# controller_rev4_2.net
KiCad netlist of a schematic drawn in EAGLE
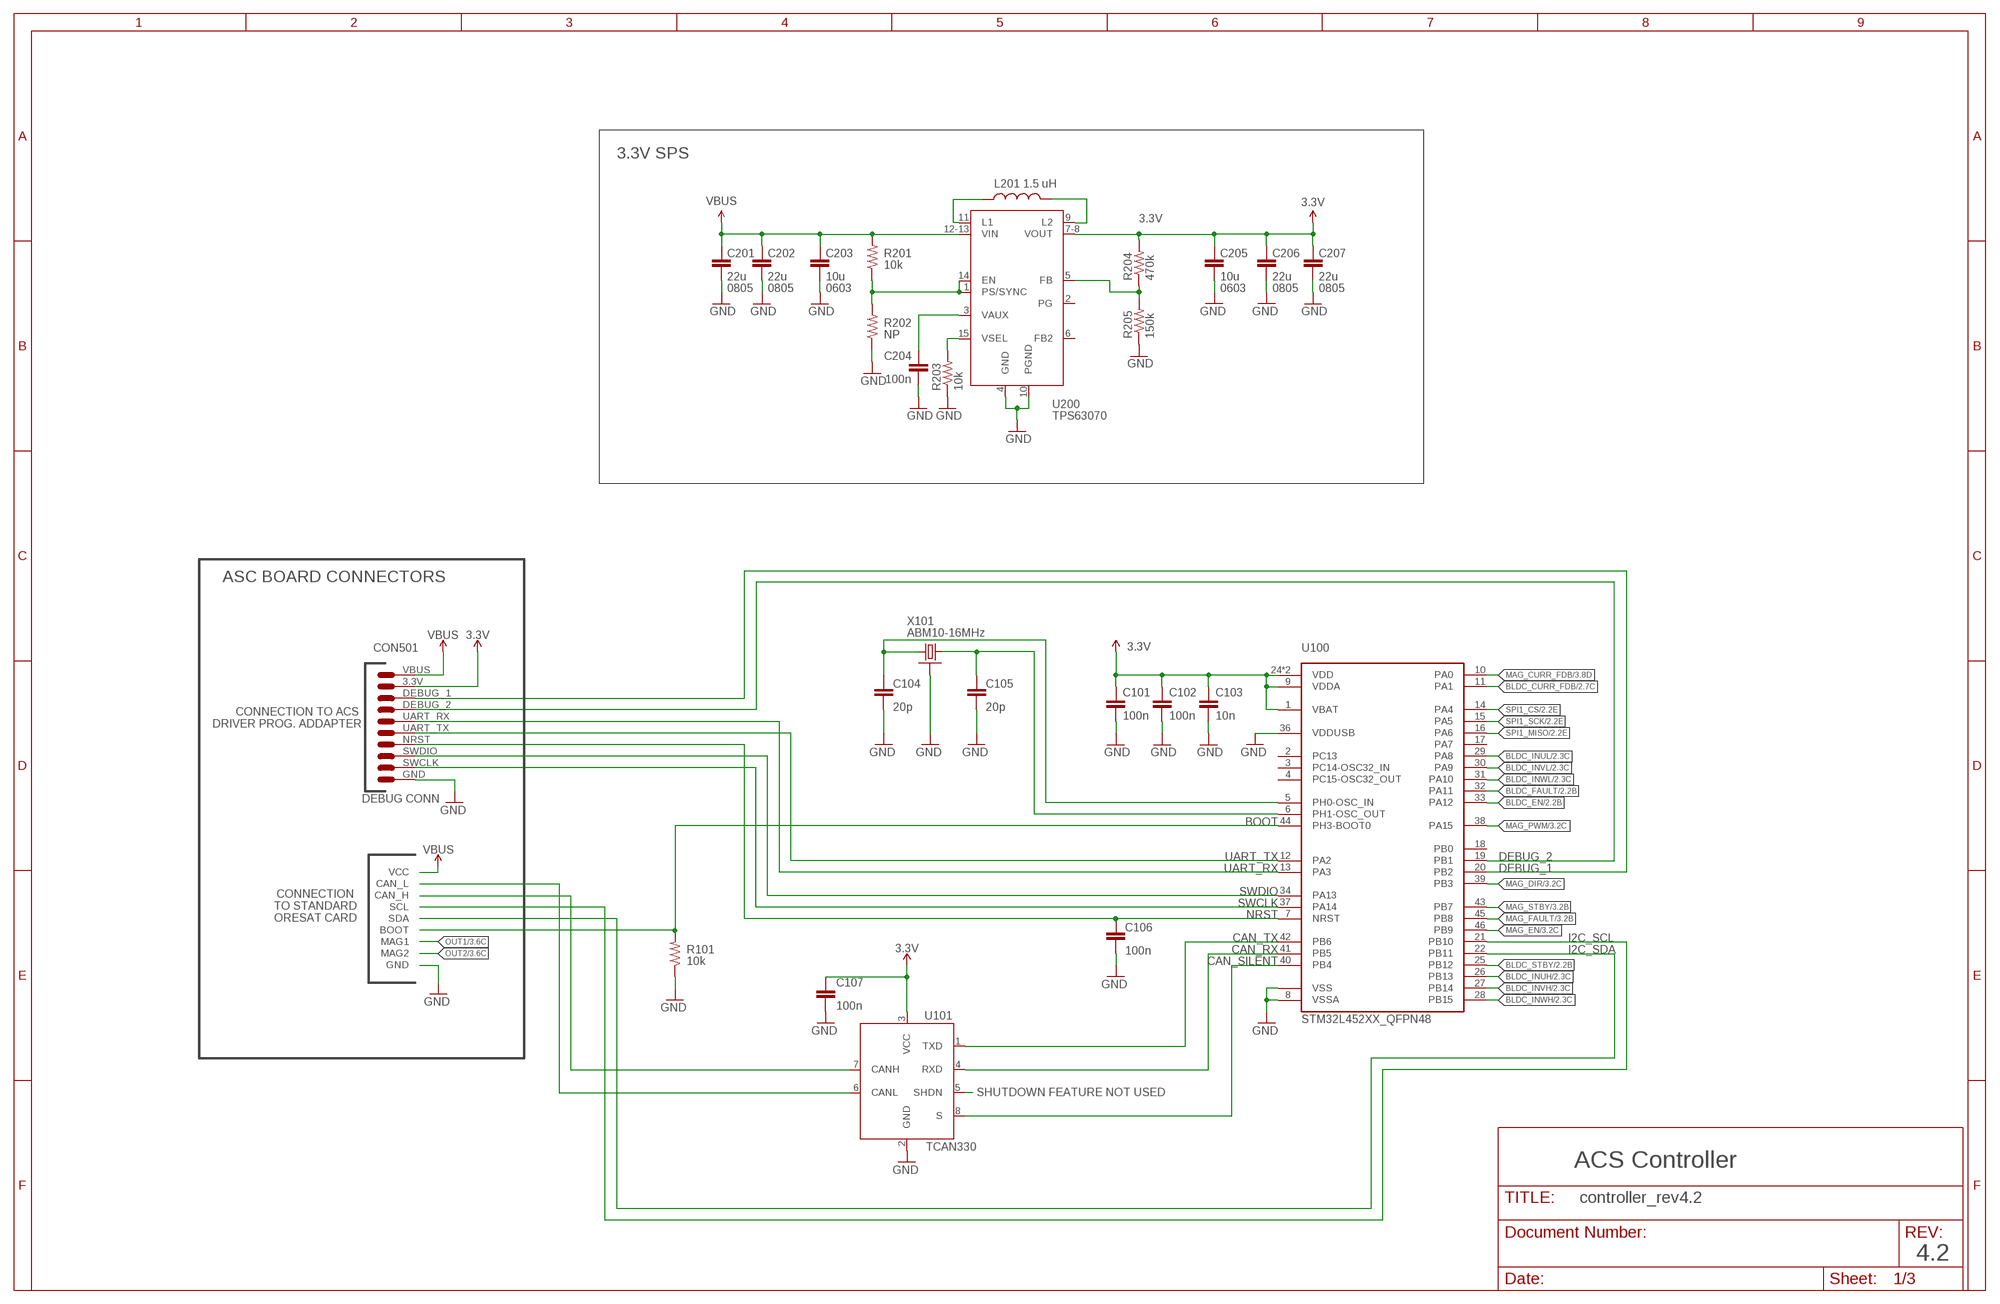
[diagram p0: schematic, sheet 1]
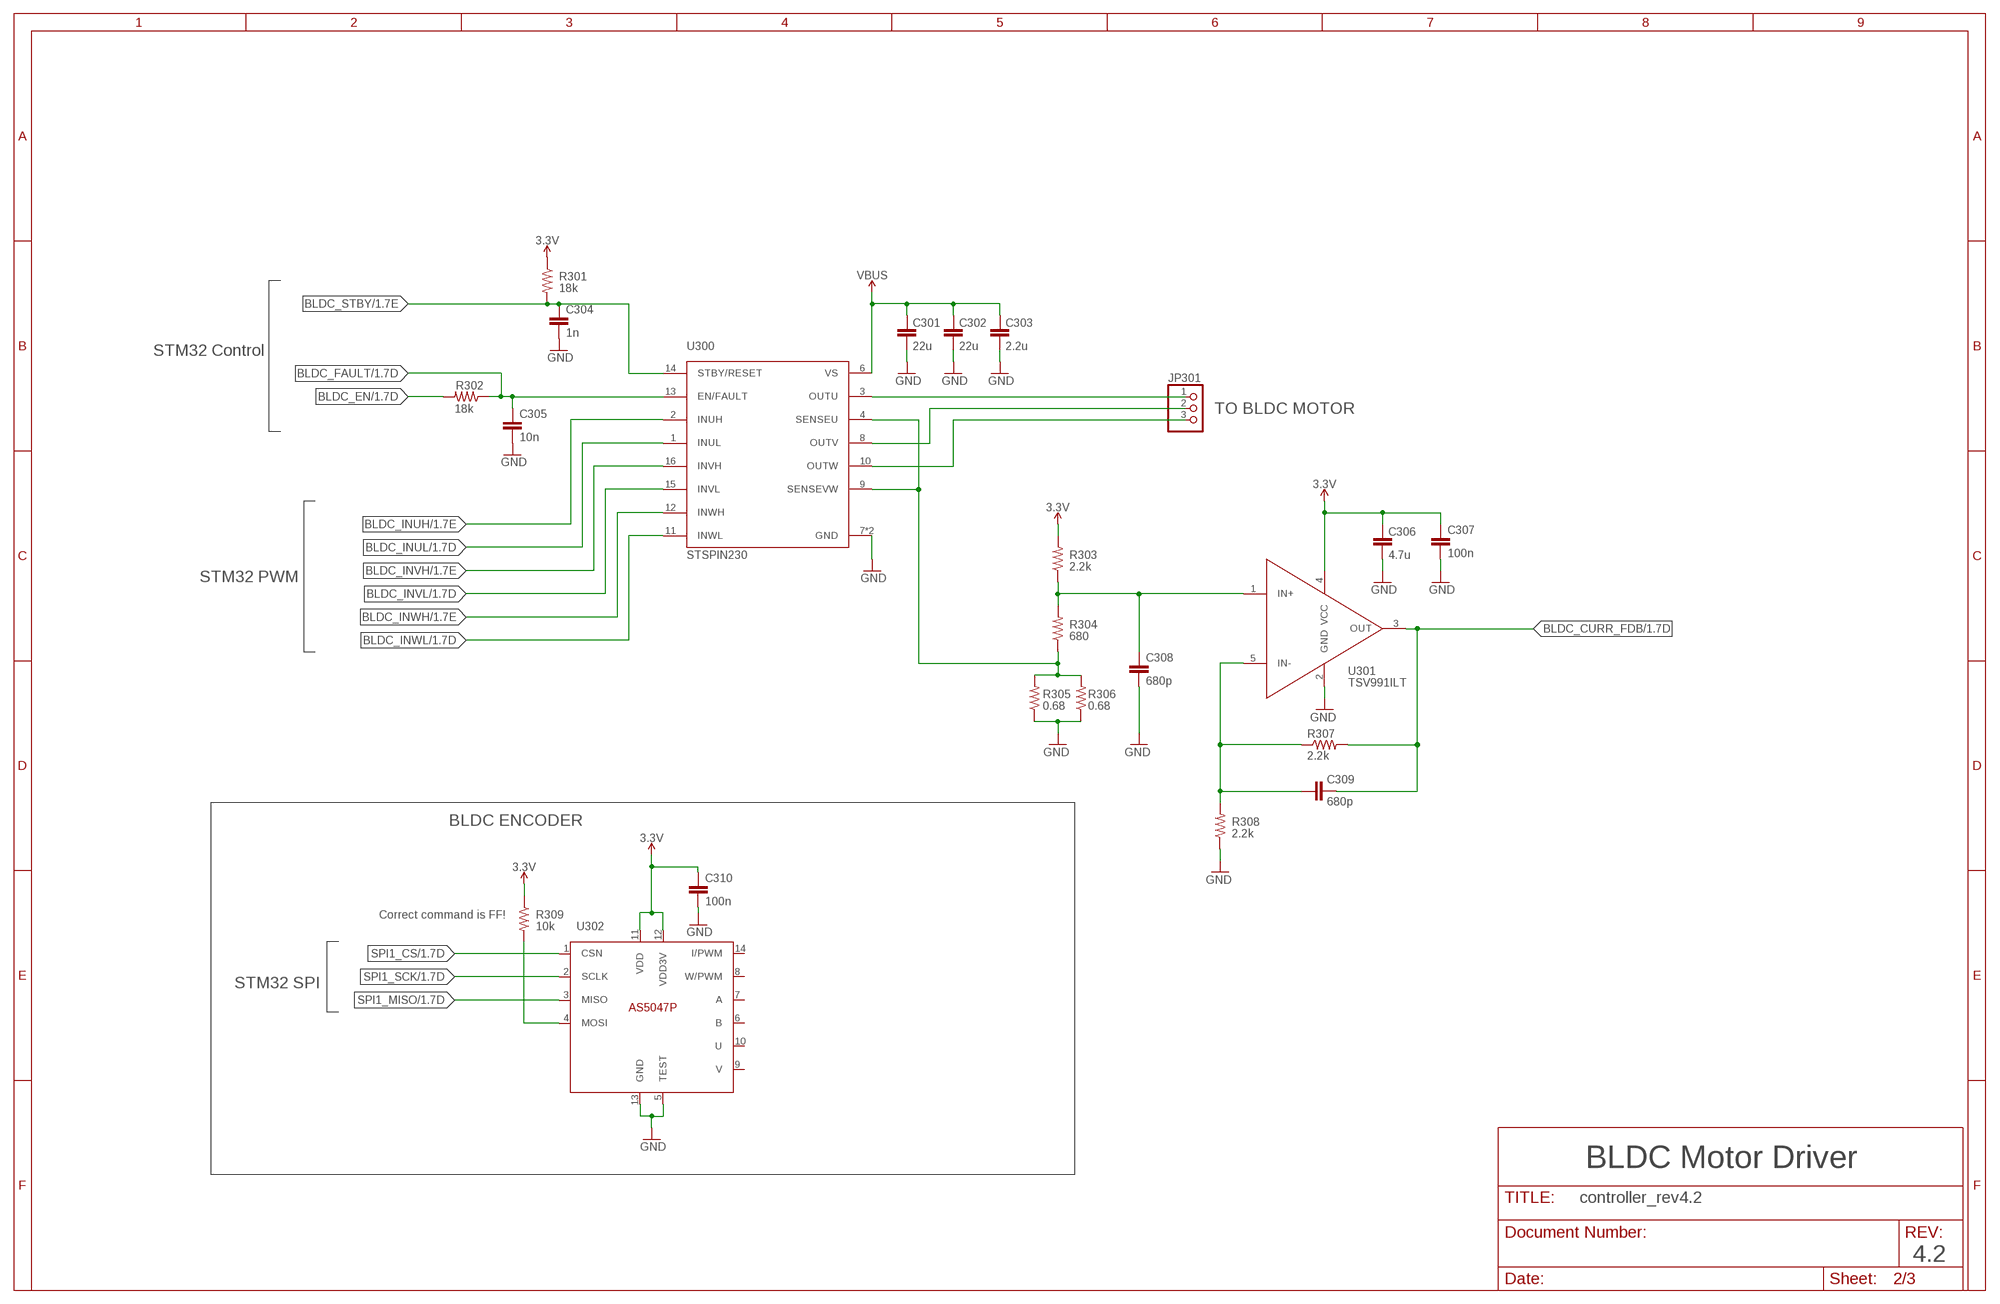
[diagram p1: schematic, sheet 2]
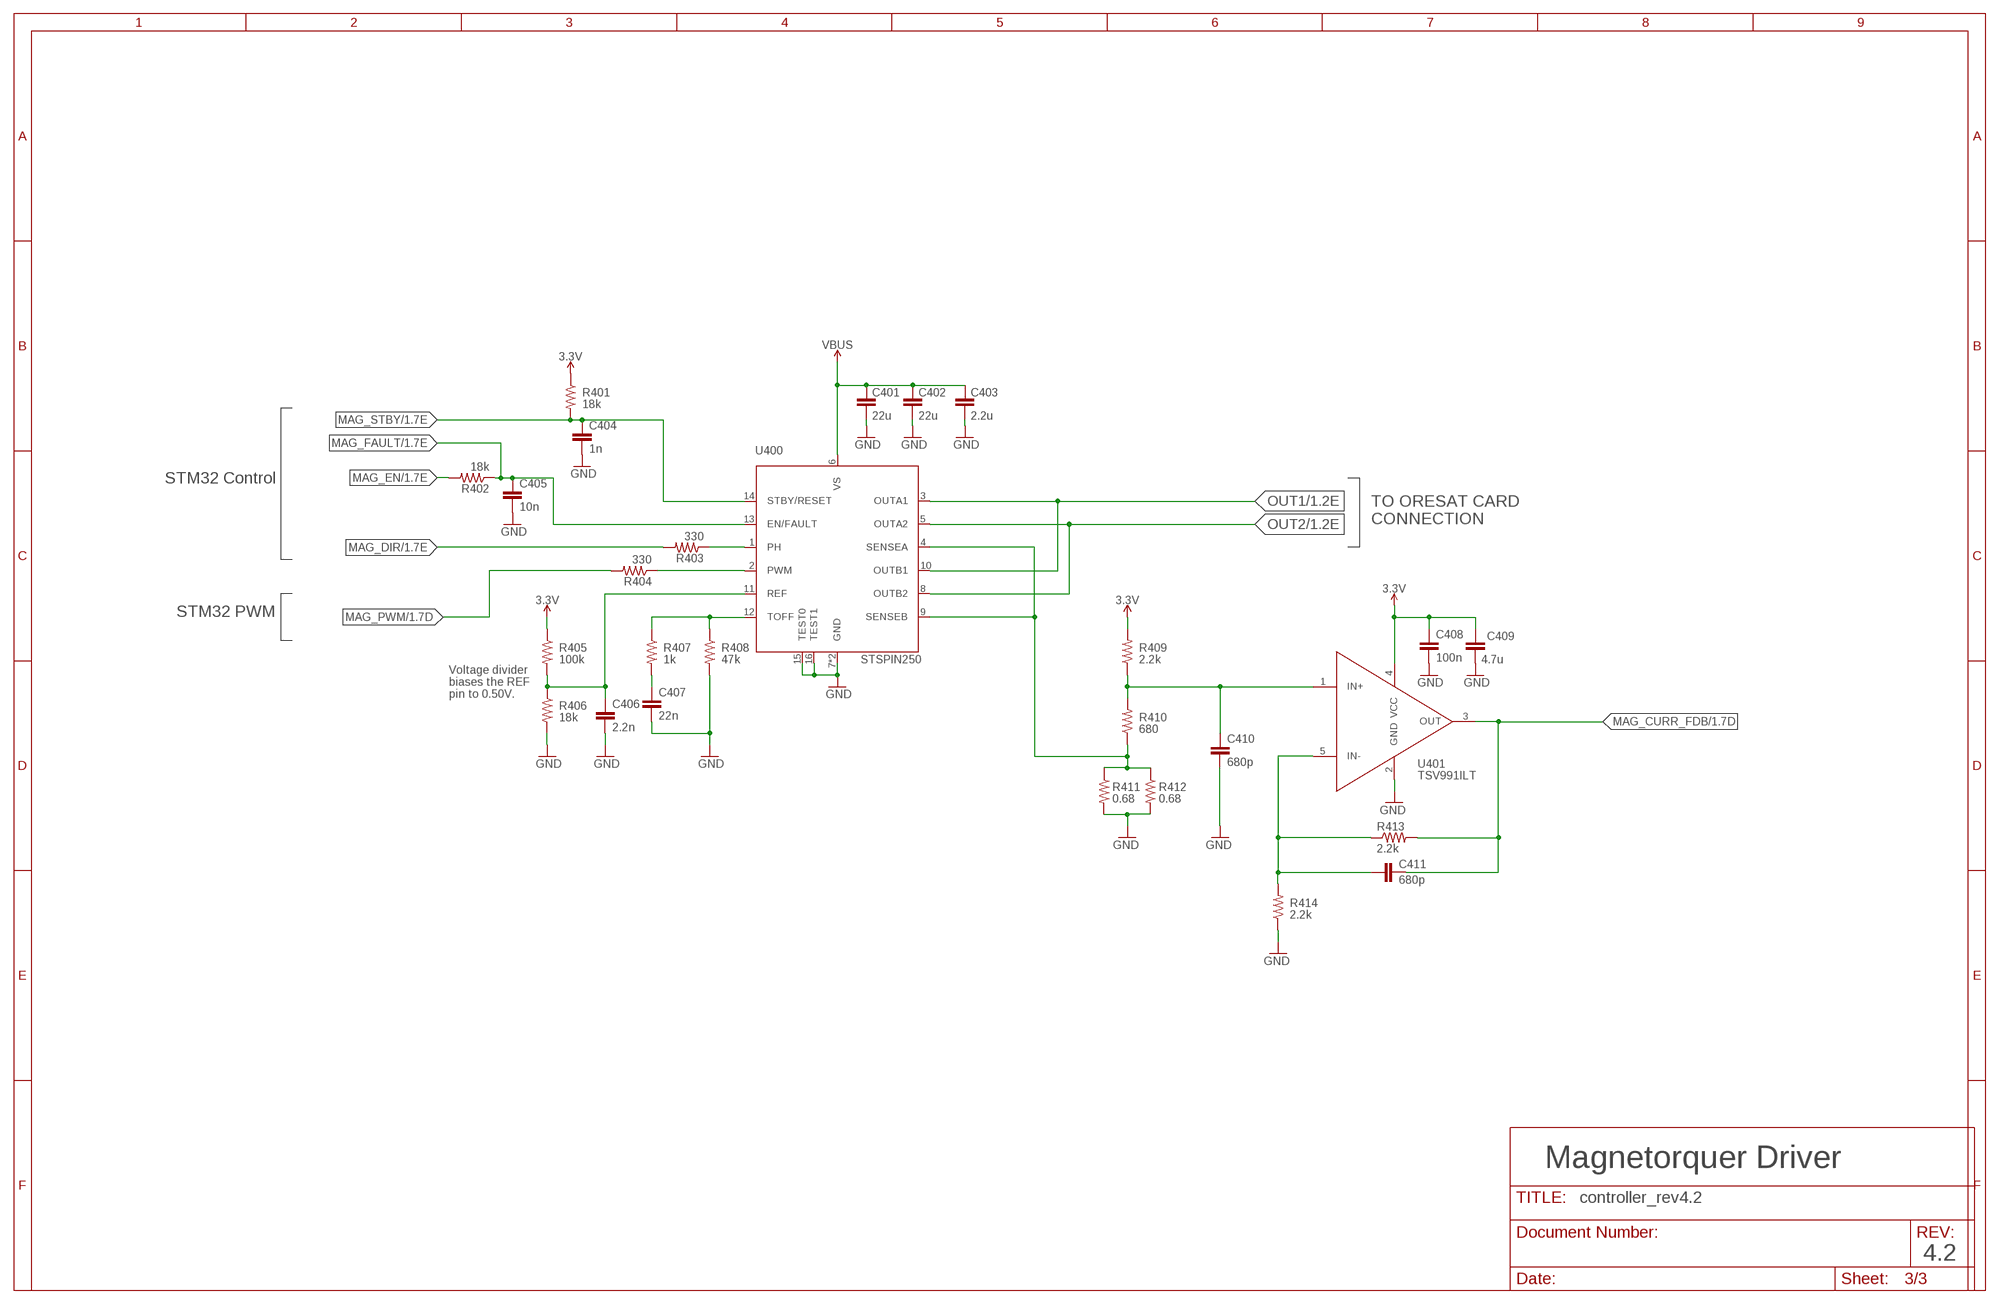
[diagram p2: schematic, sheet 3]

(export (version "E")
  (design (tool "Eeschema 10.0.6"))
  (components
    (comp (ref "C301")
      (value "22u")
      (footprint "eagle-import:.0603-B-NOSILK")
      (fields (field (name "MFR") "Samsung") (field (name "MPN") "CL05B104KO5NNNC"))
      (libsource (lib "eagle-import") (part "C-EU0603-B-NOSILK"))
    )
    (comp (ref "C302")
      (value "22u")
      (footprint "eagle-import:.0603-B-NOSILK")
      (fields (field (name "MFR") "Samsung") (field (name "MPN") "CL05B104KO5NNNC"))
      (libsource (lib "eagle-import") (part "C-EU0603-B-NOSILK"))
    )
    (comp (ref "C303")
      (value "2.2u")
      (footprint "eagle-import:.0603-B-NOSILK")
      (fields (field (name "MFR") "Samsung") (field (name "MPN") "CL05B104KO5NNNC"))
      (libsource (lib "eagle-import") (part "C-EU0603-B-NOSILK"))
    )
    (comp (ref "C304")
      (value "1n")
      (footprint "eagle-import:.0402-B-NOSILK")
      (fields (field (name "MFR") "Samsung") (field (name "MPN") "CL05B104KO5NNNC"))
      (libsource (lib "eagle-import") (part "rcl_custom_C-EU0402-B-NOSILK"))
    )
    (comp (ref "C305")
      (value "10n")
      (footprint "eagle-import:.0402-B-NOSILK")
      (fields (field (name "MFR") "Samsung") (field (name "MPN") "CL05B104KO5NNNC"))
      (libsource (lib "eagle-import") (part "rcl_custom_C-EU0402-B-NOSILK"))
    )
    (comp (ref "C306")
      (value "4.7u")
      (footprint "eagle-import:.0603-B-NOSILK")
      (fields (field (name "MFR") "Samsung") (field (name "MPN") "CL05B104KO5NNNC"))
      (libsource (lib "eagle-import") (part "C-EU0603-B-NOSILK"))
    )
    (comp (ref "C307")
      (value "100n")
      (footprint "eagle-import:.0402-B-NOSILK")
      (fields (field (name "MFR") "Samsung") (field (name "MPN") "CL05B104KO5NNNC"))
      (libsource (lib "eagle-import") (part "rcl_custom_C-EU0402-B-NOSILK"))
    )
    (comp (ref "C308")
      (value "680p")
      (footprint "eagle-import:.0402-B-NOSILK")
      (fields (field (name "MFR") "Samsung") (field (name "MPN") "CL05B104KO5NNNC"))
      (libsource (lib "eagle-import") (part "rcl_custom_C-EU0402-B-NOSILK"))
    )
    (comp (ref "C309")
      (value "680p")
      (footprint "eagle-import:.0402-B-NOSILK")
      (fields (field (name "MFR") "Samsung") (field (name "MPN") "CL05B104KO5NNNC"))
      (libsource (lib "eagle-import") (part "rcl_custom_C-EU0402-B-NOSILK"))
    )
    (comp (ref "C310")
      (value "100n")
      (footprint "eagle-import:.0402-B-NOSILK")
      (fields (field (name "MFR") "Samsung") (field (name "MPN") "CL05B104KO5NNNC"))
      (libsource (lib "eagle-import") (part "rcl_custom_C-EU0402-B-NOSILK"))
    )
    (comp (ref "JP301")
      (value "PINHD-1X03_2.00")
      (footprint "eagle-import:1X03M")
      (libsource (lib "eagle-import") (part "PINHD-1X03_2.00"))
    )
    (comp (ref "R301")
      (value "18k")
      (footprint "eagle-import:.0402-B-NOSILK")
      (fields (field (name "MFR") "Samsung") (field (name "MPN") "RC1005F6653CS"))
      (libsource (lib "eagle-import") (part "rcl_custom_R-US_0402-B-NOSILK"))
    )
    (comp (ref "R302")
      (value "18k")
      (footprint "eagle-import:.0402-B-NOSILK")
      (fields (field (name "MFR") "Samsung") (field (name "MPN") "RC1005F6653CS"))
      (libsource (lib "eagle-import") (part "rcl_custom_R-US_0402-B-NOSILK"))
    )
    (comp (ref "R303")
      (value "2.2k")
      (footprint "eagle-import:.0402-B-NOSILK")
      (fields (field (name "MFR") "Samsung") (field (name "MPN") "RC1005F6653CS"))
      (libsource (lib "eagle-import") (part "rcl_custom_R-US_0402-B-NOSILK"))
    )
    (comp (ref "R304")
      (value "680")
      (footprint "eagle-import:.0402-B-NOSILK")
      (fields (field (name "MFR") "Samsung") (field (name "MPN") "RC1005F6653CS"))
      (libsource (lib "eagle-import") (part "rcl_custom_R-US_0402-B-NOSILK"))
    )
    (comp (ref "R305")
      (value "0.68")
      (footprint "eagle-import:.0805-B-NOSILK")
      (libsource (lib "eagle-import") (part "R-US_0805-B-NOSILK"))
    )
    (comp (ref "R306")
      (value "0.68")
      (footprint "eagle-import:.0805-B-NOSILK")
      (libsource (lib "eagle-import") (part "R-US_0805-B-NOSILK"))
    )
    (comp (ref "R307")
      (value "2.2k")
      (footprint "eagle-import:.0402-B-NOSILK")
      (fields (field (name "MFR") "Samsung") (field (name "MPN") "RC1005F6653CS"))
      (libsource (lib "eagle-import") (part "rcl_custom_R-US_0402-B-NOSILK"))
    )
    (comp (ref "R308")
      (value "2.2k")
      (footprint "eagle-import:.0402-B-NOSILK")
      (fields (field (name "MFR") "Samsung") (field (name "MPN") "RC1005F6653CS"))
      (libsource (lib "eagle-import") (part "rcl_custom_R-US_0402-B-NOSILK"))
    )
    (comp (ref "R309")
      (value "10k")
      (footprint "eagle-import:.0402-B-NOSILK")
      (fields (field (name "MFR") "Samsung") (field (name "MPN") "RC1005F6653CS"))
      (libsource (lib "eagle-import") (part "rcl_custom_R-US_0402-B-NOSILK"))
    )
    (comp (ref "U300")
      (value "STSPIN230")
      (footprint "eagle-import:VFQPN")
      (libsource (lib "eagle-import") (part "STSPIN230"))
    )
    (comp (ref "U301")
      (value "TSV991ILT")
      (footprint "eagle-import:SOT23-5")
      (libsource (lib "eagle-import") (part "TSV991ILT"))
    )
    (comp (ref "U302")
      (value "AS5047P")
      (footprint "eagle-import:TSSOP14")
      (libsource (lib "eagle-import") (part "AS5047P"))
    )
    (comp (ref "C401")
      (value "22u")
      (footprint "eagle-import:.0603-B-NOSILK")
      (fields (field (name "MFR") "Samsung") (field (name "MPN") "CL05B104KO5NNNC"))
      (libsource (lib "eagle-import") (part "C-EU0603-B-NOSILK"))
    )
    (comp (ref "C402")
      (value "22u")
      (footprint "eagle-import:.0603-B-NOSILK")
      (fields (field (name "MFR") "Samsung") (field (name "MPN") "CL05B104KO5NNNC"))
      (libsource (lib "eagle-import") (part "C-EU0603-B-NOSILK"))
    )
    (comp (ref "C403")
      (value "2.2u")
      (footprint "eagle-import:.0603-B-NOSILK")
      (fields (field (name "MFR") "Samsung") (field (name "MPN") "CL05B104KO5NNNC"))
      (libsource (lib "eagle-import") (part "C-EU0603-B-NOSILK"))
    )
    (comp (ref "C404")
      (value "1n")
      (footprint "eagle-import:.0402-B-NOSILK")
      (fields (field (name "MFR") "Samsung") (field (name "MPN") "CL05B104KO5NNNC"))
      (libsource (lib "eagle-import") (part "rcl_custom_C-EU0402-B-NOSILK"))
    )
    (comp (ref "C405")
      (value "10n")
      (footprint "eagle-import:.0402-B-NOSILK")
      (fields (field (name "MFR") "Samsung") (field (name "MPN") "CL05B104KO5NNNC"))
      (libsource (lib "eagle-import") (part "rcl_custom_C-EU0402-B-NOSILK"))
    )
    (comp (ref "C406")
      (value "2.2n")
      (footprint "eagle-import:.0402-B-NOSILK")
      (fields (field (name "MFR") "Samsung") (field (name "MPN") "CL05B104KO5NNNC"))
      (libsource (lib "eagle-import") (part "rcl_custom_C-EU0402-B-NOSILK"))
    )
    (comp (ref "C407")
      (value "22n")
      (footprint "eagle-import:.0402-B-NOSILK")
      (fields (field (name "MFR") "Samsung") (field (name "MPN") "CL05B104KO5NNNC"))
      (libsource (lib "eagle-import") (part "rcl_custom_C-EU0402-B-NOSILK"))
    )
    (comp (ref "C408")
      (value "100n")
      (footprint "eagle-import:.0402-B-NOSILK")
      (fields (field (name "MFR") "Samsung") (field (name "MPN") "CL05B104KO5NNNC"))
      (libsource (lib "eagle-import") (part "rcl_custom_C-EU0402-B-NOSILK"))
    )
    (comp (ref "C409")
      (value "4.7u")
      (footprint "eagle-import:.0603-B-NOSILK")
      (fields (field (name "MFR") "Samsung") (field (name "MPN") "CL05B104KO5NNNC"))
      (libsource (lib "eagle-import") (part "C-EU0603-B-NOSILK"))
    )
    (comp (ref "C410")
      (value "680p")
      (footprint "eagle-import:.0402-B-NOSILK")
      (fields (field (name "MFR") "Samsung") (field (name "MPN") "CL05B104KO5NNNC"))
      (libsource (lib "eagle-import") (part "rcl_custom_C-EU0402-B-NOSILK"))
    )
    (comp (ref "C411")
      (value "680p")
      (footprint "eagle-import:.0402-B-NOSILK")
      (fields (field (name "MFR") "Samsung") (field (name "MPN") "CL05B104KO5NNNC"))
      (libsource (lib "eagle-import") (part "rcl_custom_C-EU0402-B-NOSILK"))
    )
    (comp (ref "R401")
      (value "18k")
      (footprint "eagle-import:.0402-B-NOSILK")
      (fields (field (name "MFR") "Samsung") (field (name "MPN") "RC1005F6653CS"))
      (libsource (lib "eagle-import") (part "rcl_custom_R-US_0402-B-NOSILK"))
    )
    (comp (ref "R402")
      (value "18k")
      (footprint "eagle-import:.0402-B-NOSILK")
      (fields (field (name "MFR") "Samsung") (field (name "MPN") "RC1005F6653CS"))
      (libsource (lib "eagle-import") (part "rcl_custom_R-US_0402-B-NOSILK"))
    )
    (comp (ref "R403")
      (value "330")
      (footprint "eagle-import:.0402-B-NOSILK")
      (fields (field (name "MFR") "Samsung") (field (name "MPN") "RC1005F6653CS"))
      (libsource (lib "eagle-import") (part "rcl_custom_R-US_0402-B-NOSILK"))
    )
    (comp (ref "R404")
      (value "330")
      (footprint "eagle-import:.0402-B-NOSILK")
      (fields (field (name "MFR") "Samsung") (field (name "MPN") "RC1005F6653CS"))
      (libsource (lib "eagle-import") (part "rcl_custom_R-US_0402-B-NOSILK"))
    )
    (comp (ref "R405")
      (value "100k")
      (footprint "eagle-import:.0402-B-NOSILK")
      (fields (field (name "MFR") "Samsung") (field (name "MPN") "RC1005F6653CS"))
      (libsource (lib "eagle-import") (part "rcl_custom_R-US_0402-B-NOSILK"))
    )
    (comp (ref "R406")
      (value "18k")
      (footprint "eagle-import:.0402-B-NOSILK")
      (fields (field (name "MFR") "Samsung") (field (name "MPN") "RC1005F6653CS"))
      (libsource (lib "eagle-import") (part "rcl_custom_R-US_0402-B-NOSILK"))
    )
    (comp (ref "R407")
      (value "1k")
      (footprint "eagle-import:.0402-B-NOSILK")
      (fields (field (name "MFR") "Samsung") (field (name "MPN") "RC1005F6653CS"))
      (libsource (lib "eagle-import") (part "rcl_custom_R-US_0402-B-NOSILK"))
    )
    (comp (ref "R408")
      (value "47k")
      (footprint "eagle-import:.0402-B-NOSILK")
      (fields (field (name "MFR") "Samsung") (field (name "MPN") "RC1005F6653CS"))
      (libsource (lib "eagle-import") (part "rcl_custom_R-US_0402-B-NOSILK"))
    )
    (comp (ref "R409")
      (value "2.2k")
      (footprint "eagle-import:.0402-B-NOSILK")
      (fields (field (name "MFR") "Samsung") (field (name "MPN") "RC1005F6653CS"))
      (libsource (lib "eagle-import") (part "rcl_custom_R-US_0402-B-NOSILK"))
    )
    (comp (ref "R410")
      (value "680")
      (footprint "eagle-import:.0402-B-NOSILK")
      (fields (field (name "MFR") "Samsung") (field (name "MPN") "RC1005F6653CS"))
      (libsource (lib "eagle-import") (part "rcl_custom_R-US_0402-B-NOSILK"))
    )
    (comp (ref "R411")
      (value "0.68")
      (footprint "eagle-import:.0805-B-NOSILK")
      (libsource (lib "eagle-import") (part "R-US_0805-B-NOSILK"))
    )
    (comp (ref "R412")
      (value "0.68")
      (footprint "eagle-import:.0805-B-NOSILK")
      (libsource (lib "eagle-import") (part "R-US_0805-B-NOSILK"))
    )
    (comp (ref "R413")
      (value "2.2k")
      (footprint "eagle-import:.0402-B-NOSILK")
      (fields (field (name "MFR") "Samsung") (field (name "MPN") "RC1005F6653CS"))
      (libsource (lib "eagle-import") (part "rcl_custom_R-US_0402-B-NOSILK"))
    )
    (comp (ref "R414")
      (value "2.2k")
      (footprint "eagle-import:.0402-B-NOSILK")
      (fields (field (name "MFR") "Samsung") (field (name "MPN") "RC1005F6653CS"))
      (libsource (lib "eagle-import") (part "rcl_custom_R-US_0402-B-NOSILK"))
    )
    (comp (ref "U400")
      (value "STSPIN250")
      (footprint "eagle-import:VFQPN")
      (libsource (lib "eagle-import") (part "STSPIN250"))
    )
    (comp (ref "U401")
      (value "TSV991ILT")
      (footprint "eagle-import:SOT23-5")
      (libsource (lib "eagle-import") (part "TSV991ILT"))
    )
    (comp (ref "C101")
      (value "100n")
      (footprint "eagle-import:.0402-B-NOSILK")
      (fields (field (name "MFR") "Samsung") (field (name "MPN") "CL05B104KO5NNNC"))
      (libsource (lib "eagle-import") (part "rcl_custom_C-EU0402-B-NOSILK"))
    )
    (comp (ref "C102")
      (value "100n")
      (footprint "eagle-import:.0402-B-NOSILK")
      (fields (field (name "MFR") "Samsung") (field (name "MPN") "CL05B104KO5NNNC"))
      (libsource (lib "eagle-import") (part "rcl_custom_C-EU0402-B-NOSILK"))
    )
    (comp (ref "C103")
      (value "10n")
      (footprint "eagle-import:.0402-B-NOSILK")
      (fields (field (name "MFR") "Samsung") (field (name "MPN") "CL05B104KO5NNNC"))
      (libsource (lib "eagle-import") (part "rcl_custom_C-EU0402-B-NOSILK"))
    )
    (comp (ref "C104")
      (value "20p")
      (footprint "eagle-import:.0402-B-NOSILK")
      (fields (field (name "MFR") "Samsung") (field (name "MPN") "CL05C200JB51PNC"))
      (libsource (lib "eagle-import") (part "rcl_custom_C-EU0402-B-NOSILK"))
    )
    (comp (ref "C105")
      (value "20p")
      (footprint "eagle-import:.0402-B-NOSILK")
      (fields (field (name "MFR") "Samsung") (field (name "MPN") "CL05C200JB51PNC"))
      (libsource (lib "eagle-import") (part "rcl_custom_C-EU0402-B-NOSILK"))
    )
    (comp (ref "C106")
      (value "100n")
      (footprint "eagle-import:.0402-B-NOSILK")
      (fields (field (name "MFR") "Samsung") (field (name "MPN") "CL05C200JB51PNC"))
      (libsource (lib "eagle-import") (part "rcl_custom_C-EU0402-B-NOSILK"))
    )
    (comp (ref "C107")
      (value "100n")
      (footprint "eagle-import:.0402-B-NOSILK")
      (fields (field (name "MFR") "Samsung") (field (name "MPN") "CL05B104KO5NNNC"))
      (libsource (lib "eagle-import") (part "rcl_custom_C-EU0402-B-NOSILK"))
    )
    (comp (ref "C201")
      (value "22u")
      (footprint "eagle-import:.0805-B-NOSILK")
      (libsource (lib "eagle-import") (part "C-EU0805-B-NOSILK"))
    )
    (comp (ref "C202")
      (value "22u")
      (footprint "eagle-import:.0805-B-NOSILK")
      (libsource (lib "eagle-import") (part "C-EU0805-B-NOSILK"))
    )
    (comp (ref "C203")
      (value "10u")
      (footprint "eagle-import:.0603-B-NOSILK")
      (fields (field (name "MFR") "Samsung") (field (name "MPN") "CL05B104KO5NNNC"))
      (libsource (lib "eagle-import") (part "C-EU0603-B-NOSILK"))
    )
    (comp (ref "C204")
      (value "100n")
      (footprint "eagle-import:.0402-B-NOSILK")
      (fields (field (name "MFR") "Samsung") (field (name "MPN") "CL05B104KO5NNNC"))
      (libsource (lib "eagle-import") (part "rcl_custom_C-EU0402-B-NOSILK"))
    )
    (comp (ref "C205")
      (value "10u")
      (footprint "eagle-import:.0603-B-NOSILK")
      (fields (field (name "MFR") "Samsung") (field (name "MPN") "CL05B104KO5NNNC"))
      (libsource (lib "eagle-import") (part "C-EU0603-B-NOSILK"))
    )
    (comp (ref "C206")
      (value "22u")
      (footprint "eagle-import:.0805-B-NOSILK")
      (libsource (lib "eagle-import") (part "C-EU0805-B-NOSILK"))
    )
    (comp (ref "C207")
      (value "22u")
      (footprint "eagle-import:.0805-B-NOSILK")
      (libsource (lib "eagle-import") (part "C-EU0805-B-NOSILK"))
    )
    (comp (ref "C501")
      (value "DEBUG_CON")
      (footprint "eagle-import:DEBUG_CON")
      (libsource (lib "eagle-import") (part "DEBUG_CON"))
    )
    (comp (ref "L201")
      (value "1.5 uH")
      (footprint "eagle-import:L-COILCRAFT-XFL4020")
      (fields (field (name "MFR") "Coilcraft") (field (name "MPN") "XFL4020-152ME"))
      (libsource (lib "eagle-import") (part "L-COILCRAFT-XFL4020"))
    )
    (comp (ref "R101")
      (value "10k")
      (footprint "eagle-import:.0402-B-NOSILK")
      (fields (field (name "MFR") "Samsung") (field (name "MPN") "RC1005F6653CS"))
      (libsource (lib "eagle-import") (part "rcl_custom_R-US_0402-B-NOSILK"))
    )
    (comp (ref "R201")
      (value "10k")
      (footprint "eagle-import:.0402-B-NOSILK")
      (fields (field (name "MFR") "Samsung") (field (name "MPN") "RC1005F6653CS"))
      (libsource (lib "eagle-import") (part "rcl_custom_R-US_0402-B-NOSILK"))
    )
    (comp (ref "R202")
      (value "NP")
      (footprint "eagle-import:.0402-B-NOSILK")
      (fields (field (name "MFR") "Samsung") (field (name "MPN") "RC1005F6653CS"))
      (libsource (lib "eagle-import") (part "rcl_custom_R-US_0402-B-NOSILK"))
    )
    (comp (ref "R203")
      (value "10k")
      (footprint "eagle-import:.0402-B-NOSILK")
      (fields (field (name "MFR") "Samsung") (field (name "MPN") "RC1005F6653CS"))
      (libsource (lib "eagle-import") (part "rcl_custom_R-US_0402-B-NOSILK"))
    )
    (comp (ref "R204")
      (value "470k")
      (footprint "eagle-import:.0402-B-NOSILK")
      (fields (field (name "MFR") "Samsung") (field (name "MPN") "RC1005F6653CS"))
      (libsource (lib "eagle-import") (part "rcl_custom_R-US_0402-B-NOSILK"))
    )
    (comp (ref "R205")
      (value "150k")
      (footprint "eagle-import:.0402-B-NOSILK")
      (fields (field (name "MFR") "Samsung") (field (name "MPN") "RC1005F6653CS"))
      (libsource (lib "eagle-import") (part "rcl_custom_R-US_0402-B-NOSILK"))
    )
    (comp (ref "U$1")
      (value "DRIVER-FLEX_CONN")
      (footprint "eagle-import:20-PAD_DRIVER-CONN")
      (libsource (lib "eagle-import") (part "DRIVER-FLEX_CONN"))
    )
    (comp (ref "U100")
      (value "STM32L452XX_QFPN48")
      (footprint "eagle-import:QFPN-48")
      (libsource (lib "eagle-import") (part "STM32L452XX_QFPN48"))
    )
    (comp (ref "U101")
      (value "TCAN330")
      (footprint "eagle-import:SOT23-8_TI-DCN")
      (fields (field (name "MFR") "Texas Instruments") (field (name "MPN") "TCAN330GDCNT"))
      (libsource (lib "eagle-import") (part "TCAN330"))
    )
    (comp (ref "U200")
      (value "TPS63070")
      (footprint "eagle-import:TPS63070X")
      (fields (field (name "MFR") "TI"))
      (libsource (lib "eagle-import") (part "TPS63070X"))
    )
    (comp (ref "X101")
      (value "ABM10-16MHz")
      (footprint "eagle-import:CRYSTAL_2.5X2")
      (fields (field (name "MFR") "ECS Inc.") (field (name "MPN") "ECS-160-10-36Q-ES-TR"))
      (libsource (lib "eagle-import") (part "CRYSTAL-WITH-GND"))
    )
  )
  (nets
    (net (code "1") (name "3.3V") (class "Default")
      (node (ref "C101") (pin "1") (pinfunction "1_1") (pintype "passive"))
      (node (ref "C102") (pin "1") (pinfunction "1_1") (pintype "passive"))
      (node (ref "C103") (pin "1") (pinfunction "1_1") (pintype "passive"))
      (node (ref "C107") (pin "1") (pinfunction "1_1") (pintype "passive"))
      (node (ref "C205") (pin "1") (pinfunction "1_1") (pintype "passive"))
      (node (ref "C206") (pin "1") (pinfunction "1_1") (pintype "passive"))
      (node (ref "C207") (pin "1") (pinfunction "1_1") (pintype "passive"))
      (node (ref "C306") (pin "1") (pinfunction "1_1") (pintype "passive"))
      (node (ref "C307") (pin "1") (pinfunction "1_1") (pintype "passive"))
      (node (ref "C310") (pin "1") (pinfunction "1_1") (pintype "passive"))
      (node (ref "C408") (pin "1") (pinfunction "1_1") (pintype "passive"))
      (node (ref "C409") (pin "1") (pinfunction "1_1") (pintype "passive"))
      (node (ref "C501") (pin "3.3V") (pinfunction "2_3.3V") (pintype "bidirectional"))
      (node (ref "R204") (pin "2") (pinfunction "2_2") (pintype "passive"))
      (node (ref "R301") (pin "1") (pinfunction "1_1") (pintype "passive"))
      (node (ref "R303") (pin "2") (pinfunction "2_2") (pintype "passive"))
      (node (ref "R309") (pin "1") (pinfunction "1_1") (pintype "passive"))
      (node (ref "R401") (pin "1") (pinfunction "1_1") (pintype "passive"))
      (node (ref "R405") (pin "1") (pinfunction "1_1") (pintype "passive"))
      (node (ref "R409") (pin "2") (pinfunction "2_2") (pintype "passive"))
      (node (ref "U100") (pin "1") (pinfunction "VBAT_1") (pintype "bidirectional"))
      (node (ref "U100") (pin "24") (pinfunction "VDD_24") (pintype "bidirectional"))
      (node (ref "U100") (pin "48") (pinfunction "VDD_48") (pintype "bidirectional"))
      (node (ref "U100") (pin "9") (pinfunction "VDDA_9") (pintype "bidirectional"))
      (node (ref "U101") (pin "3") (pinfunction "VCC_3") (pintype "power_in"))
      (node (ref "U200") (pin "7-8") (pinfunction "VOUT_7-8") (pintype "power_in"))
      (node (ref "U301") (pin "4") (pinfunction "VCC_4") (pintype "bidirectional"))
      (node (ref "U302") (pin "11") (pinfunction "VDD_11") (pintype "power_in"))
      (node (ref "U302") (pin "12") (pinfunction "VDD3V_12") (pintype "power_in"))
      (node (ref "U401") (pin "4") (pinfunction "VCC_4") (pintype "bidirectional"))
    )
    (net (code "2") (name "BLDC_CURR_FDB") (class "Default")
      (node (ref "C309") (pin "1") (pinfunction "1_1") (pintype "passive"))
      (node (ref "R307") (pin "2") (pinfunction "2_2") (pintype "passive"))
      (node (ref "U100") (pin "11") (pinfunction "PA1_11") (pintype "bidirectional"))
      (node (ref "U301") (pin "3") (pinfunction "OUT_3") (pintype "bidirectional"))
    )
    (net (code "3") (name "BLDC_EN") (class "Default")
      (node (ref "R302") (pin "2") (pinfunction "2_2") (pintype "passive"))
      (node (ref "U100") (pin "33") (pinfunction "PA12_33") (pintype "bidirectional"))
    )
    (net (code "4") (name "BLDC_FAULT") (class "Default")
      (node (ref "C305") (pin "1") (pinfunction "1_1") (pintype "passive"))
      (node (ref "R302") (pin "1") (pinfunction "1_1") (pintype "passive"))
      (node (ref "U100") (pin "32") (pinfunction "PA11_32") (pintype "bidirectional"))
      (node (ref "U300") (pin "13") (pinfunction "EN/FAULT_13") (pintype "bidirectional"))
    )
    (net (code "5") (name "BLDC_INUH") (class "Default")
      (node (ref "U100") (pin "26") (pinfunction "PB13_26") (pintype "bidirectional"))
      (node (ref "U300") (pin "2") (pinfunction "INUH_2") (pintype "input"))
    )
    (net (code "6") (name "BLDC_INUL") (class "Default")
      (node (ref "U100") (pin "29") (pinfunction "PA8_29") (pintype "bidirectional"))
      (node (ref "U300") (pin "1") (pinfunction "INUL_1") (pintype "input"))
    )
    (net (code "7") (name "BLDC_INVH") (class "Default")
      (node (ref "U100") (pin "27") (pinfunction "PB14_27") (pintype "bidirectional"))
      (node (ref "U300") (pin "16") (pinfunction "INVH_16") (pintype "input"))
    )
    (net (code "8") (name "BLDC_INVL") (class "Default")
      (node (ref "U100") (pin "30") (pinfunction "PA9_30") (pintype "bidirectional"))
      (node (ref "U300") (pin "15") (pinfunction "INVL_15") (pintype "input"))
    )
    (net (code "9") (name "BLDC_INWH") (class "Default")
      (node (ref "U100") (pin "28") (pinfunction "PB15_28") (pintype "bidirectional"))
      (node (ref "U300") (pin "12") (pinfunction "INWH_12") (pintype "input"))
    )
    (net (code "10") (name "BLDC_INWL") (class "Default")
      (node (ref "U100") (pin "31") (pinfunction "PA10_31") (pintype "bidirectional"))
      (node (ref "U300") (pin "11") (pinfunction "INWL_11") (pintype "input"))
    )
    (net (code "11") (name "BLDC_STBY") (class "Default")
      (node (ref "C304") (pin "1") (pinfunction "1_1") (pintype "passive"))
      (node (ref "R301") (pin "2") (pinfunction "2_2") (pintype "passive"))
      (node (ref "U100") (pin "25") (pinfunction "PB12_25") (pintype "bidirectional"))
      (node (ref "U300") (pin "14") (pinfunction "STBY/RESET_14") (pintype "input"))
    )
    (net (code "12") (name "BOOT") (class "Default")
      (node (ref "R101") (pin "2") (pinfunction "2_2") (pintype "passive"))
      (node (ref "U$1") (pin "BOOT") (pinfunction "BOOT_BOOT") (pintype "bidirectional"))
      (node (ref "U100") (pin "44") (pinfunction "PH3-BOOT0_44") (pintype "bidirectional"))
    )
    (net (code "13") (name "CAN_RX") (class "Default")
      (node (ref "U100") (pin "41") (pinfunction "PB5_41") (pintype "bidirectional"))
      (node (ref "U101") (pin "4") (pinfunction "RXD_4") (pintype "output"))
    )
    (net (code "14") (name "CAN_SILENT") (class "Default")
      (node (ref "U100") (pin "40") (pinfunction "PB4_40") (pintype "bidirectional"))
      (node (ref "U101") (pin "8") (pinfunction "S_8") (pintype "input"))
    )
    (net (code "15") (name "CAN_TX") (class "Default")
      (node (ref "U100") (pin "42") (pinfunction "PB6_42") (pintype "bidirectional"))
      (node (ref "U101") (pin "1") (pinfunction "TXD_1") (pintype "input"))
    )
    (net (code "16") (name "DEBUG_1") (class "Default")
      (node (ref "C501") (pin "DEBUG_1") (pinfunction "3_DEBUG_1") (pintype "bidirectional"))
      (node (ref "U100") (pin "20") (pinfunction "PB2_20") (pintype "bidirectional"))
    )
    (net (code "17") (name "DEBUG_2") (class "Default")
      (node (ref "C501") (pin "DEBUG_2") (pinfunction "4_DEBUG_2") (pintype "bidirectional"))
      (node (ref "U100") (pin "19") (pinfunction "PB1_19") (pintype "bidirectional"))
    )
    (net (code "18") (name "GND") (class "Default")
      (node (ref "C101") (pin "2") (pinfunction "2_2") (pintype "passive"))
      (node (ref "C102") (pin "2") (pinfunction "2_2") (pintype "passive"))
      (node (ref "C103") (pin "2") (pinfunction "2_2") (pintype "passive"))
      (node (ref "C104") (pin "2") (pinfunction "2_2") (pintype "passive"))
      (node (ref "C105") (pin "2") (pinfunction "2_2") (pintype "passive"))
      (node (ref "C106") (pin "2") (pinfunction "2_2") (pintype "passive"))
      (node (ref "C107") (pin "2") (pinfunction "2_2") (pintype "passive"))
      (node (ref "C201") (pin "2") (pinfunction "2_2") (pintype "passive"))
      (node (ref "C202") (pin "2") (pinfunction "2_2") (pintype "passive"))
      (node (ref "C203") (pin "2") (pinfunction "2_2") (pintype "passive"))
      (node (ref "C204") (pin "2") (pinfunction "2_2") (pintype "passive"))
      (node (ref "C205") (pin "2") (pinfunction "2_2") (pintype "passive"))
      (node (ref "C206") (pin "2") (pinfunction "2_2") (pintype "passive"))
      (node (ref "C207") (pin "2") (pinfunction "2_2") (pintype "passive"))
      (node (ref "C301") (pin "2") (pinfunction "2_2") (pintype "passive"))
      (node (ref "C302") (pin "2") (pinfunction "2_2") (pintype "passive"))
      (node (ref "C303") (pin "2") (pinfunction "2_2") (pintype "passive"))
      (node (ref "C304") (pin "2") (pinfunction "2_2") (pintype "passive"))
      (node (ref "C305") (pin "2") (pinfunction "2_2") (pintype "passive"))
      (node (ref "C306") (pin "2") (pinfunction "2_2") (pintype "passive"))
      (node (ref "C307") (pin "2") (pinfunction "2_2") (pintype "passive"))
      (node (ref "C308") (pin "2") (pinfunction "2_2") (pintype "passive"))
      (node (ref "C310") (pin "2") (pinfunction "2_2") (pintype "passive"))
      (node (ref "C401") (pin "2") (pinfunction "2_2") (pintype "passive"))
      (node (ref "C402") (pin "2") (pinfunction "2_2") (pintype "passive"))
      (node (ref "C403") (pin "2") (pinfunction "2_2") (pintype "passive"))
      (node (ref "C404") (pin "2") (pinfunction "2_2") (pintype "passive"))
      (node (ref "C405") (pin "2") (pinfunction "2_2") (pintype "passive"))
      (node (ref "C406") (pin "2") (pinfunction "2_2") (pintype "passive"))
      (node (ref "C407") (pin "2") (pinfunction "2_2") (pintype "passive"))
      (node (ref "C408") (pin "2") (pinfunction "2_2") (pintype "passive"))
      (node (ref "C409") (pin "2") (pinfunction "2_2") (pintype "passive"))
      (node (ref "C410") (pin "2") (pinfunction "2_2") (pintype "passive"))
      (node (ref "C501") (pin "GND") (pinfunction "10_GND") (pintype "bidirectional"))
      (node (ref "R101") (pin "1") (pinfunction "1_1") (pintype "passive"))
      (node (ref "R202") (pin "1") (pinfunction "1_1") (pintype "passive"))
      (node (ref "R203") (pin "1") (pinfunction "1_1") (pintype "passive"))
      (node (ref "R205") (pin "1") (pinfunction "1_1") (pintype "passive"))
      (node (ref "R305") (pin "1") (pinfunction "1_1") (pintype "passive"))
      (node (ref "R306") (pin "1") (pinfunction "1_1") (pintype "passive"))
      (node (ref "R308") (pin "1") (pinfunction "1_1") (pintype "passive"))
      (node (ref "R406") (pin "2") (pinfunction "2_2") (pintype "passive"))
      (node (ref "R408") (pin "2") (pinfunction "2_2") (pintype "passive"))
      (node (ref "R411") (pin "2") (pinfunction "2_2") (pintype "passive"))
      (node (ref "R412") (pin "2") (pinfunction "2_2") (pintype "passive"))
      (node (ref "R414") (pin "1") (pinfunction "1_1") (pintype "passive"))
      (node (ref "U$1") (pin "GND1") (pinfunction "GND_GND1") (pintype "bidirectional"))
      (node (ref "U$1") (pin "GND2") (pinfunction "GND_GND2") (pintype "bidirectional"))
      (node (ref "U$1") (pin "GND3") (pinfunction "GND_GND3") (pintype "bidirectional"))
      (node (ref "U$1") (pin "GND4") (pinfunction "GND_GND4") (pintype "bidirectional"))
      (node (ref "U$1") (pin "GND5") (pinfunction "GND_GND5") (pintype "bidirectional"))
      (node (ref "U$1") (pin "GND6") (pinfunction "GND_GND6") (pintype "bidirectional"))
      (node (ref "U$1") (pin "GND7") (pinfunction "GND_GND7") (pintype "bidirectional"))
      (node (ref "U$1") (pin "GND8") (pinfunction "GND_GND8") (pintype "bidirectional"))
      (node (ref "U$1") (pin "GND9") (pinfunction "GND_GND9") (pintype "bidirectional"))
      (node (ref "U100") (pin "23") (pinfunction "VSS_23") (pintype "bidirectional"))
      (node (ref "U100") (pin "35") (pinfunction "VSS_35") (pintype "bidirectional"))
      (node (ref "U100") (pin "36") (pinfunction "VDDUSB_36") (pintype "bidirectional"))
      (node (ref "U100") (pin "47") (pinfunction "VSS_47") (pintype "bidirectional"))
      (node (ref "U100") (pin "8") (pinfunction "VSSA_8") (pintype "bidirectional"))
      (node (ref "U100") (pin "EPAD") (pinfunction "VSS_EPAD") (pintype "bidirectional"))
      (node (ref "U101") (pin "2") (pinfunction "GND_2") (pintype "power_in"))
      (node (ref "U200") (pin "10") (pinfunction "PGND_10") (pintype "power_in"))
      (node (ref "U200") (pin "4") (pinfunction "GND_4") (pintype "power_in"))
      (node (ref "U300") (pin "7") (pinfunction "GND_7") (pintype "power_in"))
      (node (ref "U300") (pin "EPAD") (pinfunction "GND_EPAD") (pintype "power_in"))
      (node (ref "U301") (pin "2") (pinfunction "GND_2") (pintype "bidirectional"))
      (node (ref "U302") (pin "13") (pinfunction "GND_13") (pintype "power_in"))
      (node (ref "U302") (pin "5") (pinfunction "TEST_5") (pintype "power_in"))
      (node (ref "U400") (pin "15") (pinfunction "TEST0_15") (pintype "bidirectional"))
      (node (ref "U400") (pin "16") (pinfunction "TEST1_16") (pintype "bidirectional"))
      (node (ref "U400") (pin "7") (pinfunction "GND_7") (pintype "power_in"))
      (node (ref "U400") (pin "EPAD") (pinfunction "GND_EPAD") (pintype "power_in"))
      (node (ref "U401") (pin "2") (pinfunction "GND_2") (pintype "bidirectional"))
      (node (ref "X101") (pin "2") (pinfunction "SHIELD_2") (pintype "power_in"))
      (node (ref "X101") (pin "4") (pinfunction "SHIELD_4") (pintype "power_in"))
    )
    (net (code "19") (name "I2C_SCL") (class "Default")
      (node (ref "U$1") (pin "SCL") (pinfunction "SCL_SCL") (pintype "bidirectional"))
      (node (ref "U100") (pin "21") (pinfunction "PB10_21") (pintype "bidirectional"))
    )
    (net (code "20") (name "I2C_SDA") (class "Default")
      (node (ref "U$1") (pin "SDA") (pinfunction "SDA_SDA") (pintype "bidirectional"))
      (node (ref "U100") (pin "22") (pinfunction "PB11_22") (pintype "bidirectional"))
    )
    (net (code "21") (name "MAG_CURR_FDB") (class "Default")
      (node (ref "C411") (pin "1") (pinfunction "1_1") (pintype "passive"))
      (node (ref "R413") (pin "2") (pinfunction "2_2") (pintype "passive"))
      (node (ref "U100") (pin "10") (pinfunction "PA0_10") (pintype "bidirectional"))
      (node (ref "U401") (pin "3") (pinfunction "OUT_3") (pintype "bidirectional"))
    )
    (net (code "22") (name "MAG_DIR") (class "Default")
      (node (ref "R403") (pin "2") (pinfunction "2_2") (pintype "passive"))
      (node (ref "U100") (pin "39") (pinfunction "PB3_39") (pintype "bidirectional"))
    )
    (net (code "23") (name "MAG_EN") (class "Default")
      (node (ref "R402") (pin "2") (pinfunction "2_2") (pintype "passive"))
      (node (ref "U100") (pin "46") (pinfunction "PB9_46") (pintype "bidirectional"))
    )
    (net (code "24") (name "MAG_FAULT") (class "Default")
      (node (ref "C405") (pin "1") (pinfunction "1_1") (pintype "passive"))
      (node (ref "R402") (pin "1") (pinfunction "1_1") (pintype "passive"))
      (node (ref "U100") (pin "45") (pinfunction "PB8_45") (pintype "bidirectional"))
      (node (ref "U400") (pin "13") (pinfunction "EN/FAULT_13") (pintype "bidirectional"))
    )
    (net (code "25") (name "MAG_PWM") (class "Default")
      (node (ref "R404") (pin "2") (pinfunction "2_2") (pintype "passive"))
      (node (ref "U100") (pin "38") (pinfunction "PA15_38") (pintype "bidirectional"))
    )
    (net (code "26") (name "MAG_STBY") (class "Default")
      (node (ref "C404") (pin "1") (pinfunction "1_1") (pintype "passive"))
      (node (ref "R401") (pin "2") (pinfunction "2_2") (pintype "passive"))
      (node (ref "U100") (pin "43") (pinfunction "PB7_43") (pintype "bidirectional"))
      (node (ref "U400") (pin "14") (pinfunction "STBY/RESET_14") (pintype "bidirectional"))
    )
    (net (code "27") (name "NRST") (class "Default")
      (node (ref "C106") (pin "1") (pinfunction "1_1") (pintype "passive"))
      (node (ref "C501") (pin "NRST") (pinfunction "7_NRST") (pintype "bidirectional"))
      (node (ref "U100") (pin "7") (pinfunction "NRST_7") (pintype "bidirectional"))
    )
    (net (code "28") (name "Net-(C407-Pad1)") (class "Default")
      (node (ref "C407") (pin "1") (pinfunction "1_1") (pintype "passive"))
      (node (ref "R407") (pin "2") (pinfunction "2_2") (pintype "passive"))
    )
    (net (code "29") (name "Net-(U100-PH0-OSC_IN)") (class "Default")
      (node (ref "C104") (pin "1") (pinfunction "1_1") (pintype "passive"))
      (node (ref "U100") (pin "5") (pinfunction "PH0-OSC_IN_5") (pintype "bidirectional"))
      (node (ref "X101") (pin "3") (pinfunction "2_3") (pintype "passive"))
    )
    (net (code "30") (name "Net-(U100-PH1-OSC_OUT)") (class "Default")
      (node (ref "C105") (pin "1") (pinfunction "1_1") (pintype "passive"))
      (node (ref "U100") (pin "6") (pinfunction "PH1-OSC_OUT_6") (pintype "bidirectional"))
      (node (ref "X101") (pin "1") (pinfunction "1_1") (pintype "passive"))
    )
    (net (code "31") (name "Net-(U101-CANH)") (class "Default")
      (node (ref "U$1") (pin "CAN_H") (pinfunction "CAN_H_CAN_H") (pintype "bidirectional"))
      (node (ref "U101") (pin "7") (pinfunction "CANH_7") (pintype "bidirectional"))
    )
    (net (code "32") (name "Net-(U101-CANL)") (class "Default")
      (node (ref "U$1") (pin "CAN_L") (pinfunction "CAN_L_CAN_L") (pintype "bidirectional"))
      (node (ref "U101") (pin "6") (pinfunction "CANL_6") (pintype "bidirectional"))
    )
    (net (code "33") (name "Net-(U200-EN)") (class "Default")
      (node (ref "R201") (pin "1") (pinfunction "1_1") (pintype "passive"))
      (node (ref "R202") (pin "2") (pinfunction "2_2") (pintype "passive"))
      (node (ref "U200") (pin "1") (pinfunction "PS/SYNC_1") (pintype "input"))
      (node (ref "U200") (pin "14") (pinfunction "EN_14") (pintype "input"))
    )
    (net (code "34") (name "Net-(U200-FB)") (class "Default")
      (node (ref "R204") (pin "1") (pinfunction "1_1") (pintype "passive"))
      (node (ref "R205") (pin "2") (pinfunction "2_2") (pintype "passive"))
      (node (ref "U200") (pin "5") (pinfunction "FB_5") (pintype "passive"))
    )
    (net (code "35") (name "Net-(U200-L1)") (class "Default")
      (node (ref "L201") (pin "1") (pinfunction "1_1") (pintype "passive"))
      (node (ref "U200") (pin "11") (pinfunction "L1_11") (pintype "passive"))
    )
    (net (code "36") (name "Net-(U200-L2)") (class "Default")
      (node (ref "L201") (pin "2") (pinfunction "2_2") (pintype "passive"))
      (node (ref "U200") (pin "9") (pinfunction "L2_9") (pintype "passive"))
    )
    (net (code "37") (name "Net-(U200-VAUX)") (class "Default")
      (node (ref "C204") (pin "1") (pinfunction "1_1") (pintype "passive"))
      (node (ref "U200") (pin "3") (pinfunction "VAUX_3") (pintype "output"))
    )
    (net (code "38") (name "Net-(U200-VSEL)") (class "Default")
      (node (ref "R203") (pin "2") (pinfunction "2_2") (pintype "passive"))
      (node (ref "U200") (pin "15") (pinfunction "VSEL_15") (pintype "input"))
    )
    (net (code "39") (name "Net-(U300-OUTU)") (class "Default")
      (node (ref "JP301") (pin "1") (pinfunction "1_1") (pintype "passive"))
      (node (ref "U300") (pin "3") (pinfunction "OUTU_3") (pintype "output"))
    )
    (net (code "40") (name "Net-(U300-OUTV)") (class "Default")
      (node (ref "JP301") (pin "2") (pinfunction "2_2") (pintype "passive"))
      (node (ref "U300") (pin "8") (pinfunction "OUTV_8") (pintype "output"))
    )
    (net (code "41") (name "Net-(U300-OUTW)") (class "Default")
      (node (ref "JP301") (pin "3") (pinfunction "3_3") (pintype "passive"))
      (node (ref "U300") (pin "10") (pinfunction "OUTW_10") (pintype "output"))
    )
    (net (code "42") (name "Net-(U300-SENSEU)") (class "Default")
      (node (ref "R304") (pin "1") (pinfunction "1_1") (pintype "passive"))
      (node (ref "R305") (pin "2") (pinfunction "2_2") (pintype "passive"))
      (node (ref "R306") (pin "2") (pinfunction "2_2") (pintype "passive"))
      (node (ref "U300") (pin "4") (pinfunction "SENSEU_4") (pintype "output"))
      (node (ref "U300") (pin "9") (pinfunction "SENSEVW_9") (pintype "output"))
    )
    (net (code "43") (name "Net-(U301-IN+)") (class "Default")
      (node (ref "C308") (pin "1") (pinfunction "1_1") (pintype "passive"))
      (node (ref "R303") (pin "1") (pinfunction "1_1") (pintype "passive"))
      (node (ref "R304") (pin "2") (pinfunction "2_2") (pintype "passive"))
      (node (ref "U301") (pin "1") (pinfunction "IN+_1") (pintype "bidirectional"))
    )
    (net (code "44") (name "Net-(U301-IN-)") (class "Default")
      (node (ref "C309") (pin "2") (pinfunction "2_2") (pintype "passive"))
      (node (ref "R307") (pin "1") (pinfunction "1_1") (pintype "passive"))
      (node (ref "R308") (pin "2") (pinfunction "2_2") (pintype "passive"))
      (node (ref "U301") (pin "5") (pinfunction "IN-_5") (pintype "bidirectional"))
    )
    (net (code "45") (name "Net-(U302-MOSI)") (class "Default")
      (node (ref "R309") (pin "2") (pinfunction "2_2") (pintype "passive"))
      (node (ref "U302") (pin "4") (pinfunction "MOSI_4") (pintype "input"))
    )
    (net (code "46") (name "Net-(U400-PH)") (class "Default")
      (node (ref "R403") (pin "1") (pinfunction "1_1") (pintype "passive"))
      (node (ref "U400") (pin "1") (pinfunction "PH_1") (pintype "input"))
    )
    (net (code "47") (name "Net-(U400-PWM)") (class "Default")
      (node (ref "R404") (pin "1") (pinfunction "1_1") (pintype "passive"))
      (node (ref "U400") (pin "2") (pinfunction "PWM_2") (pintype "input"))
    )
    (net (code "48") (name "Net-(U400-REF)") (class "Default")
      (node (ref "C406") (pin "1") (pinfunction "1_1") (pintype "passive"))
      (node (ref "R405") (pin "2") (pinfunction "2_2") (pintype "passive"))
      (node (ref "R406") (pin "1") (pinfunction "1_1") (pintype "passive"))
      (node (ref "U400") (pin "11") (pinfunction "REF_11") (pintype "passive"))
    )
    (net (code "49") (name "Net-(U400-SENSEA)") (class "Default")
      (node (ref "R410") (pin "1") (pinfunction "1_1") (pintype "passive"))
      (node (ref "R411") (pin "1") (pinfunction "1_1") (pintype "passive"))
      (node (ref "R412") (pin "1") (pinfunction "1_1") (pintype "passive"))
      (node (ref "U400") (pin "4") (pinfunction "SENSEA_4") (pintype "output"))
      (node (ref "U400") (pin "9") (pinfunction "SENSEB_9") (pintype "output"))
    )
    (net (code "50") (name "Net-(U400-TOFF)") (class "Default")
      (node (ref "R407") (pin "1") (pinfunction "1_1") (pintype "passive"))
      (node (ref "R408") (pin "1") (pinfunction "1_1") (pintype "passive"))
      (node (ref "U400") (pin "12") (pinfunction "TOFF_12") (pintype "passive"))
    )
    (net (code "51") (name "Net-(U401-IN+)") (class "Default")
      (node (ref "C410") (pin "1") (pinfunction "1_1") (pintype "passive"))
      (node (ref "R409") (pin "1") (pinfunction "1_1") (pintype "passive"))
      (node (ref "R410") (pin "2") (pinfunction "2_2") (pintype "passive"))
      (node (ref "U401") (pin "1") (pinfunction "IN+_1") (pintype "bidirectional"))
    )
    (net (code "52") (name "Net-(U401-IN-)") (class "Default")
      (node (ref "C411") (pin "2") (pinfunction "2_2") (pintype "passive"))
      (node (ref "R413") (pin "1") (pinfunction "1_1") (pintype "passive"))
      (node (ref "R414") (pin "2") (pinfunction "2_2") (pintype "passive"))
      (node (ref "U401") (pin "5") (pinfunction "IN-_5") (pintype "bidirectional"))
    )
    (net (code "53") (name "OUT1") (class "Default")
      (node (ref "U$1") (pin "MAG1") (pinfunction "MAG1_MAG1") (pintype "bidirectional"))
      (node (ref "U400") (pin "10") (pinfunction "OUTB1_10") (pintype "output"))
      (node (ref "U400") (pin "3") (pinfunction "OUTA1_3") (pintype "output"))
    )
    (net (code "54") (name "OUT2") (class "Default")
      (node (ref "U$1") (pin "MAG2") (pinfunction "MAG2_MAG2") (pintype "bidirectional"))
      (node (ref "U400") (pin "5") (pinfunction "OUTA2_5") (pintype "output"))
      (node (ref "U400") (pin "8") (pinfunction "OUTB2_8") (pintype "output"))
    )
    (net (code "55") (name "SPI1_CS") (class "Default")
      (node (ref "U100") (pin "14") (pinfunction "PA4_14") (pintype "bidirectional"))
      (node (ref "U302") (pin "1") (pinfunction "CSN_1") (pintype "input"))
    )
    (net (code "56") (name "SPI1_MISO") (class "Default")
      (node (ref "U100") (pin "16") (pinfunction "PA6_16") (pintype "bidirectional"))
      (node (ref "U302") (pin "3") (pinfunction "MISO_3") (pintype "output"))
    )
    (net (code "57") (name "SPI1_SCK") (class "Default")
      (node (ref "U100") (pin "15") (pinfunction "PA5_15") (pintype "bidirectional"))
      (node (ref "U302") (pin "2") (pinfunction "SCLK_2") (pintype "input"))
    )
    (net (code "58") (name "SWCLK") (class "Default")
      (node (ref "C501") (pin "SWCLK") (pinfunction "9_SWCLK") (pintype "bidirectional"))
      (node (ref "U100") (pin "37") (pinfunction "PA14_37") (pintype "bidirectional"))
    )
    (net (code "59") (name "SWDIO") (class "Default")
      (node (ref "C501") (pin "SWDIO") (pinfunction "8_SWDIO") (pintype "bidirectional"))
      (node (ref "U100") (pin "34") (pinfunction "PA13_34") (pintype "bidirectional"))
    )
    (net (code "60") (name "UART_RX") (class "Default")
      (node (ref "C501") (pin "UART_RX") (pinfunction "5_UART_RX") (pintype "bidirectional"))
      (node (ref "U100") (pin "13") (pinfunction "PA3_13") (pintype "bidirectional"))
    )
    (net (code "61") (name "UART_TX") (class "Default")
      (node (ref "C501") (pin "UART_TX") (pinfunction "6_UART_TX") (pintype "bidirectional"))
      (node (ref "U100") (pin "12") (pinfunction "PA2_12") (pintype "bidirectional"))
    )
    (net (code "62") (name "VBUS") (class "Default")
      (node (ref "C201") (pin "1") (pinfunction "1_1") (pintype "passive"))
      (node (ref "C202") (pin "1") (pinfunction "1_1") (pintype "passive"))
      (node (ref "C203") (pin "1") (pinfunction "1_1") (pintype "passive"))
      (node (ref "C301") (pin "1") (pinfunction "1_1") (pintype "passive"))
      (node (ref "C302") (pin "1") (pinfunction "1_1") (pintype "passive"))
      (node (ref "C303") (pin "1") (pinfunction "1_1") (pintype "passive"))
      (node (ref "C401") (pin "1") (pinfunction "1_1") (pintype "passive"))
      (node (ref "C402") (pin "1") (pinfunction "1_1") (pintype "passive"))
      (node (ref "C403") (pin "1") (pinfunction "1_1") (pintype "passive"))
      (node (ref "C501") (pin "VBUS") (pinfunction "1_VBUS") (pintype "bidirectional"))
      (node (ref "R201") (pin "2") (pinfunction "2_2") (pintype "passive"))
      (node (ref "U$1") (pin "VCC1") (pinfunction "VCC_VCC1") (pintype "bidirectional"))
      (node (ref "U$1") (pin "VCC2") (pinfunction "VCC_VCC2") (pintype "bidirectional"))
      (node (ref "U$1") (pin "VCC3") (pinfunction "VCC_VCC3") (pintype "bidirectional"))
      (node (ref "U$1") (pin "VCC4") (pinfunction "VCC_VCC4") (pintype "bidirectional"))
      (node (ref "U200") (pin "12-13") (pinfunction "VIN_12-13") (pintype "power_in"))
      (node (ref "U300") (pin "6") (pinfunction "VS_6") (pintype "power_in"))
      (node (ref "U400") (pin "6") (pinfunction "VS_6") (pintype "power_in"))
    )
    (net (code "63") (name "unconnected-(U100-PA7-Pad17)") (class "Default")
      (node (ref "U100") (pin "17") (pinfunction "PA7_17") (pintype "bidirectional"))
    )
    (net (code "64") (name "unconnected-(U100-PB0-Pad18)") (class "Default")
      (node (ref "U100") (pin "18") (pinfunction "PB0_18") (pintype "bidirectional"))
    )
    (net (code "65") (name "unconnected-(U100-PC13-Pad2)") (class "Default")
      (node (ref "U100") (pin "2") (pinfunction "PC13_2") (pintype "bidirectional"))
    )
    (net (code "66") (name "unconnected-(U100-PC14-OSC32_IN-Pad3)") (class "Default")
      (node (ref "U100") (pin "3") (pinfunction "PC14-OSC32_IN_3") (pintype "bidirectional"))
    )
    (net (code "67") (name "unconnected-(U100-PC15-OSC32_OUT-Pad4)") (class "Default")
      (node (ref "U100") (pin "4") (pinfunction "PC15-OSC32_OUT_4") (pintype "bidirectional"))
    )
    (net (code "68") (name "unconnected-(U101-SHDN-Pad5)") (class "Default")
      (node (ref "U101") (pin "5") (pinfunction "SHDN_5") (pintype "input"))
    )
    (net (code "69") (name "unconnected-(U200-FB2-Pad6)") (class "Default")
      (node (ref "U200") (pin "6") (pinfunction "FB2_6") (pintype "passive"))
    )
    (net (code "70") (name "unconnected-(U200-PG-Pad2)") (class "Default")
      (node (ref "U200") (pin "2") (pinfunction "PG_2") (pintype "open_collector"))
    )
    (net (code "71") (name "unconnected-(U302-A-Pad7)") (class "Default")
      (node (ref "U302") (pin "7") (pinfunction "A_7") (pintype "output"))
    )
    (net (code "72") (name "unconnected-(U302-B-Pad6)") (class "Default")
      (node (ref "U302") (pin "6") (pinfunction "B_6") (pintype "output"))
    )
    (net (code "73") (name "unconnected-(U302-I{slash}PWM-Pad14)") (class "Default")
      (node (ref "U302") (pin "14") (pinfunction "I/PWM_14") (pintype "output"))
    )
    (net (code "74") (name "unconnected-(U302-U-Pad10)") (class "Default")
      (node (ref "U302") (pin "10") (pinfunction "U_10") (pintype "output"))
    )
    (net (code "75") (name "unconnected-(U302-V-Pad9)") (class "Default")
      (node (ref "U302") (pin "9") (pinfunction "V_9") (pintype "output"))
    )
    (net (code "76") (name "unconnected-(U302-W{slash}PWM-Pad8)") (class "Default")
      (node (ref "U302") (pin "8") (pinfunction "W/PWM_8") (pintype "output"))
    )
  )
)
